# voltmeter.net
KiCad netlist of a schematic drawn in EAGLE
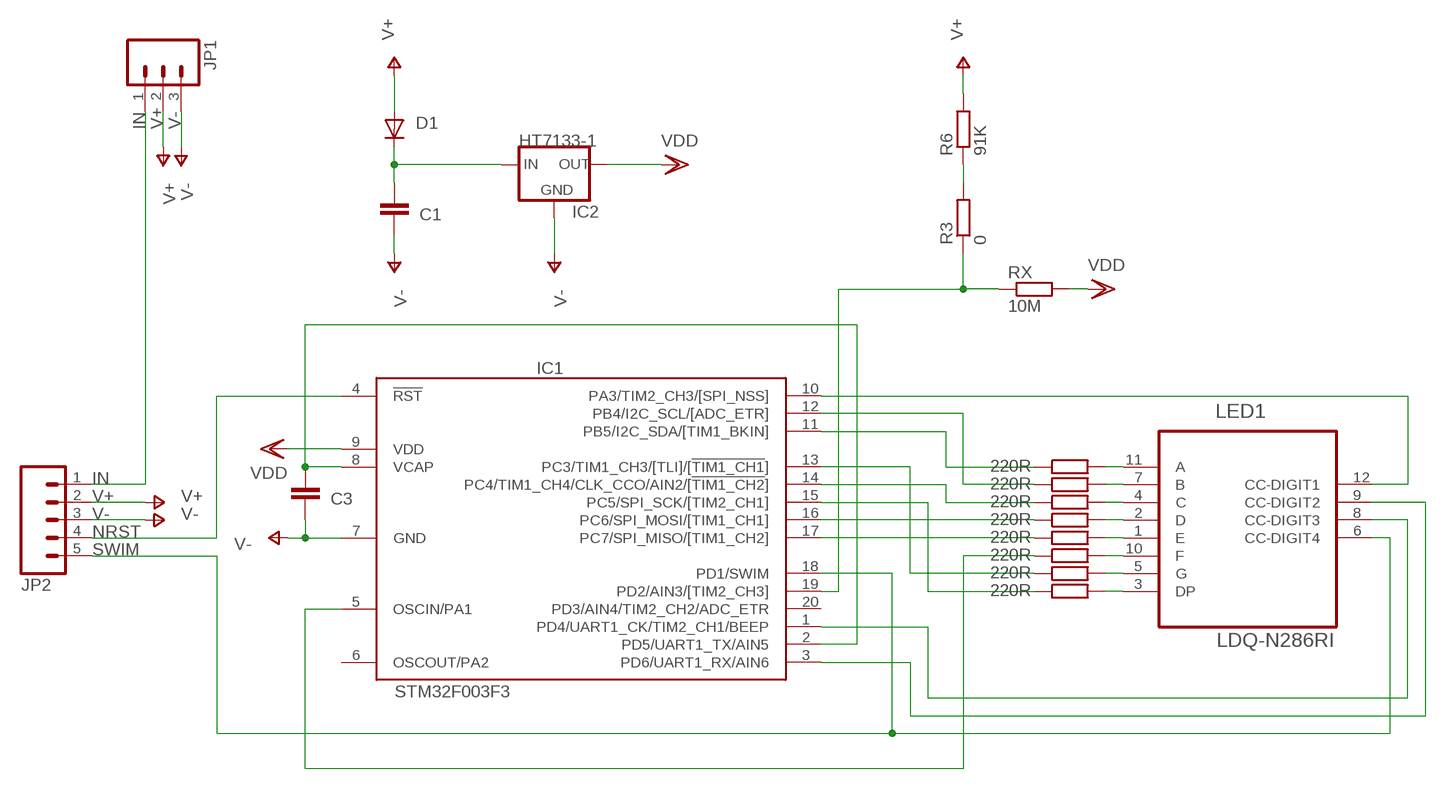
[diagram p0: schematic, sheet 1]

(export (version "E")
  (design (tool "Eeschema 10.0.6"))
  (components
    (comp (ref "C1")
      (value "C-EUC0603")
      (footprint "eagle-import:C0603")
      (libsource (lib "eagle-import") (part "C-EUC0603"))
    )
    (comp (ref "C3")
      (value "C-EUC0603")
      (footprint "eagle-import:C0603")
      (libsource (lib "eagle-import") (part "C-EUC0603"))
    )
    (comp (ref "D1")
      (value "DIODE-SOD-123")
      (footprint "eagle-import:SOD-123")
      (libsource (lib "eagle-import") (part "DIODE-SOD-123"))
    )
    (comp (ref "IC1")
      (value "STM32F003F3")
      (footprint "eagle-import:TSSOP20")
      (libsource (lib "eagle-import") (part "STM32F003F3"))
    )
    (comp (ref "IC2")
      (value "HT7133-1")
      (footprint "eagle-import:SOT89R")
      (libsource (lib "eagle-import") (part "XC63FPP"))
    )
    (comp (ref "JP1")
      (value "M03PTH")
      (footprint "eagle-import:1X03")
      (libsource (lib "eagle-import") (part "M03PTH"))
    )
    (comp (ref "JP2")
      (value "M05PTH")
      (footprint "eagle-import:1X05")
      (libsource (lib "eagle-import") (part "M05PTH"))
    )
    (comp (ref "LED1")
      (value "LDQ-N286RI")
      (footprint "eagle-import:LUMEX_LDQ-N286RI")
      (libsource (lib "eagle-import") (part "LDQ-N286RI"))
    )
    (comp (ref "R1")
      (value "220R")
      (footprint "eagle-import:R0603")
      (libsource (lib "eagle-import") (part "R-EU_R0603"))
    )
    (comp (ref "R2")
      (value "220R")
      (footprint "eagle-import:R0603")
      (libsource (lib "eagle-import") (part "R-EU_R0603"))
    )
    (comp (ref "R3")
      (value "0")
      (footprint "eagle-import:R0603")
      (libsource (lib "eagle-import") (part "R-EU_R0603"))
    )
    (comp (ref "R4")
      (value "220R")
      (footprint "eagle-import:R0603")
      (libsource (lib "eagle-import") (part "R-EU_R0603"))
    )
    (comp (ref "R5")
      (value "220R")
      (footprint "eagle-import:R0603")
      (libsource (lib "eagle-import") (part "R-EU_R0603"))
    )
    (comp (ref "R6")
      (value "91K")
      (footprint "eagle-import:R0603")
      (libsource (lib "eagle-import") (part "R-EU_R0603"))
    )
    (comp (ref "R7")
      (value "220R")
      (footprint "eagle-import:R0603")
      (libsource (lib "eagle-import") (part "R-EU_R0603"))
    )
    (comp (ref "R8")
      (value "220R")
      (footprint "eagle-import:R0603")
      (libsource (lib "eagle-import") (part "R-EU_R0603"))
    )
    (comp (ref "R13")
      (value "220R")
      (footprint "eagle-import:R0603")
      (libsource (lib "eagle-import") (part "R-EU_R0603"))
    )
    (comp (ref "R16")
      (value "220R")
      (footprint "eagle-import:R0603")
      (libsource (lib "eagle-import") (part "R-EU_R0603"))
    )
    (comp (ref "RX")
      (value "10M")
      (footprint "eagle-import:R0603")
      (libsource (lib "eagle-import") (part "R-EU_R0603"))
    )
  )
  (nets
    (net (code "1") (name "/IN") (class "Default")
      (node (ref "JP1") (pin "1") (pinfunction "1_1") (pintype "passive"))
      (node (ref "JP2") (pin "1") (pinfunction "1_1") (pintype "passive"))
    )
    (net (code "2") (name "/NRST") (class "Default")
      (node (ref "IC1") (pin "4") (pinfunction "~{RST}_4") (pintype "input"))
      (node (ref "JP2") (pin "4") (pinfunction "4_4") (pintype "passive"))
    )
    (net (code "3") (name "/SWIM") (class "Default")
      (node (ref "IC1") (pin "18") (pinfunction "PD1/SWIM_18") (pintype "bidirectional"))
      (node (ref "JP2") (pin "5") (pinfunction "5_5") (pintype "passive"))
      (node (ref "LED1") (pin "6") (pinfunction "CC-DIGIT4_6") (pintype "passive"))
    )
    (net (code "4") (name "Net-(IC1-OSCIN{slash}PA1)") (class "Default")
      (node (ref "IC1") (pin "5") (pinfunction "OSCIN/PA1_5") (pintype "bidirectional"))
      (node (ref "R16") (pin "1") (pinfunction "1_1") (pintype "passive"))
    )
    (net (code "5") (name "Net-(IC1-PA3{slash}TIM2_CH3{slash}[SPI_NSS])") (class "Default")
      (node (ref "IC1") (pin "10") (pinfunction "PA3/TIM2_CH3/[SPI_NSS]_10") (pintype "bidirectional"))
      (node (ref "LED1") (pin "12") (pinfunction "CC-DIGIT1_12") (pintype "passive"))
    )
    (net (code "6") (name "Net-(IC1-PB4{slash}I2C_SCL{slash}[ADC_ETR])") (class "Default")
      (node (ref "IC1") (pin "12") (pinfunction "PB4/I2C_SCL/[ADC_ETR]_12") (pintype "bidirectional"))
      (node (ref "R2") (pin "1") (pinfunction "1_1") (pintype "passive"))
    )
    (net (code "7") (name "Net-(IC1-PB5{slash}I2C_SDA{slash}[TIM1_BKIN])") (class "Default")
      (node (ref "IC1") (pin "11") (pinfunction "PB5/I2C_SDA/[TIM1_BKIN]_11") (pintype "bidirectional"))
      (node (ref "R1") (pin "1") (pinfunction "1_1") (pintype "passive"))
    )
    (net (code "8") (name "Net-(IC1-PC3{slash}TIM1_CH3{slash}[TLI]{slash}[~{TIM1_CH1}])") (class "Default")
      (node (ref "IC1") (pin "13") (pinfunction "PC3/TIM1_CH3/[TLI]/[~{TIM1_CH1}]_13") (pintype "bidirectional"))
      (node (ref "R7") (pin "1") (pinfunction "1_1") (pintype "passive"))
    )
    (net (code "9") (name "Net-(IC1-PC4{slash}TIM1_CH4{slash}CLK_CCO{slash}AIN2{slash}[~{TIM1_CH2}])") (class "Default")
      (node (ref "IC1") (pin "14") (pinfunction "PC4/TIM1_CH4/CLK_CCO/AIN2/[~{TIM1_CH2}]_14") (pintype "bidirectional"))
      (node (ref "R13") (pin "1") (pinfunction "1_1") (pintype "passive"))
    )
    (net (code "10") (name "Net-(IC1-PC5{slash}SPI_SCK{slash}[TIM2_CH1])") (class "Default")
      (node (ref "IC1") (pin "15") (pinfunction "PC5/SPI_SCK/[TIM2_CH1]_15") (pintype "bidirectional"))
      (node (ref "R8") (pin "1") (pinfunction "1_1") (pintype "passive"))
    )
    (net (code "11") (name "Net-(IC1-PC6{slash}SPI_MOSI{slash}[TIM1_CH1])") (class "Default")
      (node (ref "IC1") (pin "16") (pinfunction "PC6/SPI_MOSI/[TIM1_CH1]_16") (pintype "bidirectional"))
      (node (ref "R4") (pin "1") (pinfunction "1_1") (pintype "passive"))
    )
    (net (code "12") (name "Net-(IC1-PC7{slash}SPI_MISO{slash}[TIM1_CH2])") (class "Default")
      (node (ref "IC1") (pin "17") (pinfunction "PC7/SPI_MISO/[TIM1_CH2]_17") (pintype "bidirectional"))
      (node (ref "R5") (pin "1") (pinfunction "1_1") (pintype "passive"))
    )
    (net (code "13") (name "Net-(IC1-PD2{slash}AIN3{slash}[TIM2_CH3])") (class "Default")
      (node (ref "IC1") (pin "19") (pinfunction "PD2/AIN3/[TIM2_CH3]_19") (pintype "bidirectional"))
      (node (ref "R3") (pin "1") (pinfunction "1_1") (pintype "passive"))
      (node (ref "RX") (pin "1") (pinfunction "1_1") (pintype "passive"))
    )
    (net (code "14") (name "Net-(IC1-PD4{slash}UART1_CK{slash}TIM2_CH1{slash}BEEP)") (class "Default")
      (node (ref "IC1") (pin "1") (pinfunction "PD4/UART1_CK/TIM2_CH1/BEEP_1") (pintype "bidirectional"))
      (node (ref "LED1") (pin "8") (pinfunction "CC-DIGIT3_8") (pintype "passive"))
    )
    (net (code "15") (name "Net-(IC1-PD5{slash}UART1_TX{slash}AIN5)") (class "Default")
      (node (ref "C3") (pin "2") (pinfunction "2_2") (pintype "passive"))
      (node (ref "IC1") (pin "2") (pinfunction "PD5/UART1_TX/AIN5_2") (pintype "bidirectional"))
      (node (ref "IC1") (pin "8") (pinfunction "VCAP_8") (pintype "power_in"))
    )
    (net (code "16") (name "Net-(IC1-PD6{slash}UART1_RX{slash}AIN6)") (class "Default")
      (node (ref "IC1") (pin "3") (pinfunction "PD6/UART1_RX/AIN6_3") (pintype "bidirectional"))
      (node (ref "LED1") (pin "9") (pinfunction "CC-DIGIT2_9") (pintype "passive"))
    )
    (net (code "17") (name "Net-(IC2-IN)") (class "Default")
      (node (ref "C1") (pin "2") (pinfunction "2_2") (pintype "passive"))
      (node (ref "D1") (pin "C") (pinfunction "C_C") (pintype "passive"))
      (node (ref "IC2") (pin "2") (pinfunction "IN_2") (pintype "input"))
    )
    (net (code "18") (name "Net-(LED1-A)") (class "Default")
      (node (ref "LED1") (pin "11") (pinfunction "A_11") (pintype "passive"))
      (node (ref "R1") (pin "2") (pinfunction "2_2") (pintype "passive"))
    )
    (net (code "19") (name "Net-(LED1-B)") (class "Default")
      (node (ref "LED1") (pin "7") (pinfunction "B_7") (pintype "passive"))
      (node (ref "R2") (pin "2") (pinfunction "2_2") (pintype "passive"))
    )
    (net (code "20") (name "Net-(LED1-C)") (class "Default")
      (node (ref "LED1") (pin "4") (pinfunction "C_4") (pintype "passive"))
      (node (ref "R13") (pin "2") (pinfunction "2_2") (pintype "passive"))
    )
    (net (code "21") (name "Net-(LED1-D)") (class "Default")
      (node (ref "LED1") (pin "2") (pinfunction "D_2") (pintype "passive"))
      (node (ref "R4") (pin "2") (pinfunction "2_2") (pintype "passive"))
    )
    (net (code "22") (name "Net-(LED1-DP)") (class "Default")
      (node (ref "LED1") (pin "3") (pinfunction "DP_3") (pintype "passive"))
      (node (ref "R8") (pin "2") (pinfunction "2_2") (pintype "passive"))
    )
    (net (code "23") (name "Net-(LED1-E)") (class "Default")
      (node (ref "LED1") (pin "1") (pinfunction "E_1") (pintype "passive"))
      (node (ref "R5") (pin "2") (pinfunction "2_2") (pintype "passive"))
    )
    (net (code "24") (name "Net-(LED1-F)") (class "Default")
      (node (ref "LED1") (pin "10") (pinfunction "F_10") (pintype "passive"))
      (node (ref "R16") (pin "2") (pinfunction "2_2") (pintype "passive"))
    )
    (net (code "25") (name "Net-(LED1-G)") (class "Default")
      (node (ref "LED1") (pin "5") (pinfunction "G_5") (pintype "passive"))
      (node (ref "R7") (pin "2") (pinfunction "2_2") (pintype "passive"))
    )
    (net (code "26") (name "Net-(R3-Pad2)") (class "Default")
      (node (ref "R3") (pin "2") (pinfunction "2_2") (pintype "passive"))
      (node (ref "R6") (pin "1") (pinfunction "1_1") (pintype "passive"))
    )
    (net (code "27") (name "V+") (class "Default")
      (node (ref "D1") (pin "A") (pinfunction "A_A") (pintype "passive"))
      (node (ref "JP1") (pin "2") (pinfunction "2_2") (pintype "passive"))
      (node (ref "JP2") (pin "2") (pinfunction "2_2") (pintype "passive"))
      (node (ref "R6") (pin "2") (pinfunction "2_2") (pintype "passive"))
    )
    (net (code "28") (name "V-") (class "Default")
      (node (ref "C1") (pin "1") (pinfunction "1_1") (pintype "passive"))
      (node (ref "C3") (pin "1") (pinfunction "1_1") (pintype "passive"))
      (node (ref "IC1") (pin "7") (pinfunction "GND_7") (pintype "power_in"))
      (node (ref "IC2") (pin "1") (pinfunction "GND_1") (pintype "input"))
      (node (ref "JP1") (pin "3") (pinfunction "3_3") (pintype "passive"))
      (node (ref "JP2") (pin "3") (pinfunction "3_3") (pintype "passive"))
    )
    (net (code "29") (name "VDD") (class "Default")
      (node (ref "IC1") (pin "9") (pinfunction "VDD_9") (pintype "power_in"))
      (node (ref "IC2") (pin "3") (pinfunction "OUT_3") (pintype "passive"))
      (node (ref "RX") (pin "2") (pinfunction "2_2") (pintype "passive"))
    )
    (net (code "30") (name "unconnected-(IC1-OSCOUT{slash}PA2-Pad6)") (class "Default")
      (node (ref "IC1") (pin "6") (pinfunction "OSCOUT/PA2_6") (pintype "bidirectional"))
    )
    (net (code "31") (name "unconnected-(IC1-PD3{slash}AIN4{slash}TIM2_CH2{slash}ADC_ETR-Pad20)") (class "Default")
      (node (ref "IC1") (pin "20") (pinfunction "PD3/AIN4/TIM2_CH2/ADC_ETR_20") (pintype "bidirectional"))
    )
  )
)
